# Headers.net
KiCad netlist of a schematic drawn in Altium Designer
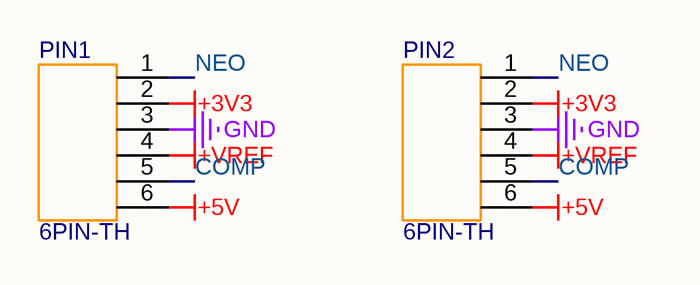
[diagram p0: Headers.SchDoc]

(export (version "E")
  (design (tool "Eeschema 10.0.6"))
  (components
    (comp (ref "PIN1") (value "6PIN-TH") (footprint "6PIN-TH") (libsource (lib "RC") (part "6PIN-TH")))
    (comp (ref "PIN2") (value "6PIN-TH") (footprint "6PIN-TH") (libsource (lib "RC") (part "6PIN-TH")))
  )
  (nets
    (net (code "1") (name "+3V3") (class "Default")
      (node (ref "PIN1") (pin "2") (pinfunction "02_2") (pintype "passive"))
      (node (ref "PIN2") (pin "2") (pinfunction "02_2") (pintype "passive"))
    )
    (net (code "2") (name "+5V") (class "Default")
      (node (ref "PIN1") (pin "6") (pinfunction "06_6") (pintype "passive"))
      (node (ref "PIN2") (pin "6") (pinfunction "06_6") (pintype "passive"))
    )
    (net (code "3") (name "+VREF") (class "Default")
      (node (ref "PIN1") (pin "4") (pinfunction "04_4") (pintype "passive"))
      (node (ref "PIN2") (pin "4") (pinfunction "04_4") (pintype "passive"))
    )
    (net (code "4") (name "/COMP") (class "Default")
      (node (ref "PIN1") (pin "5") (pinfunction "05_5") (pintype "passive"))
      (node (ref "PIN2") (pin "5") (pinfunction "05_5") (pintype "passive"))
    )
    (net (code "5") (name "/NEO") (class "Default")
      (node (ref "PIN1") (pin "1") (pinfunction "01_1") (pintype "passive"))
      (node (ref "PIN2") (pin "1") (pinfunction "01_1") (pintype "passive"))
    )
    (net (code "6") (name "GND") (class "Default")
      (node (ref "PIN1") (pin "3") (pinfunction "03_3") (pintype "passive"))
      (node (ref "PIN2") (pin "3") (pinfunction "03_3") (pintype "passive"))
    )
  )
)
